# LED_sign_board_3.net
KiCad netlist of a schematic drawn in EAGLE
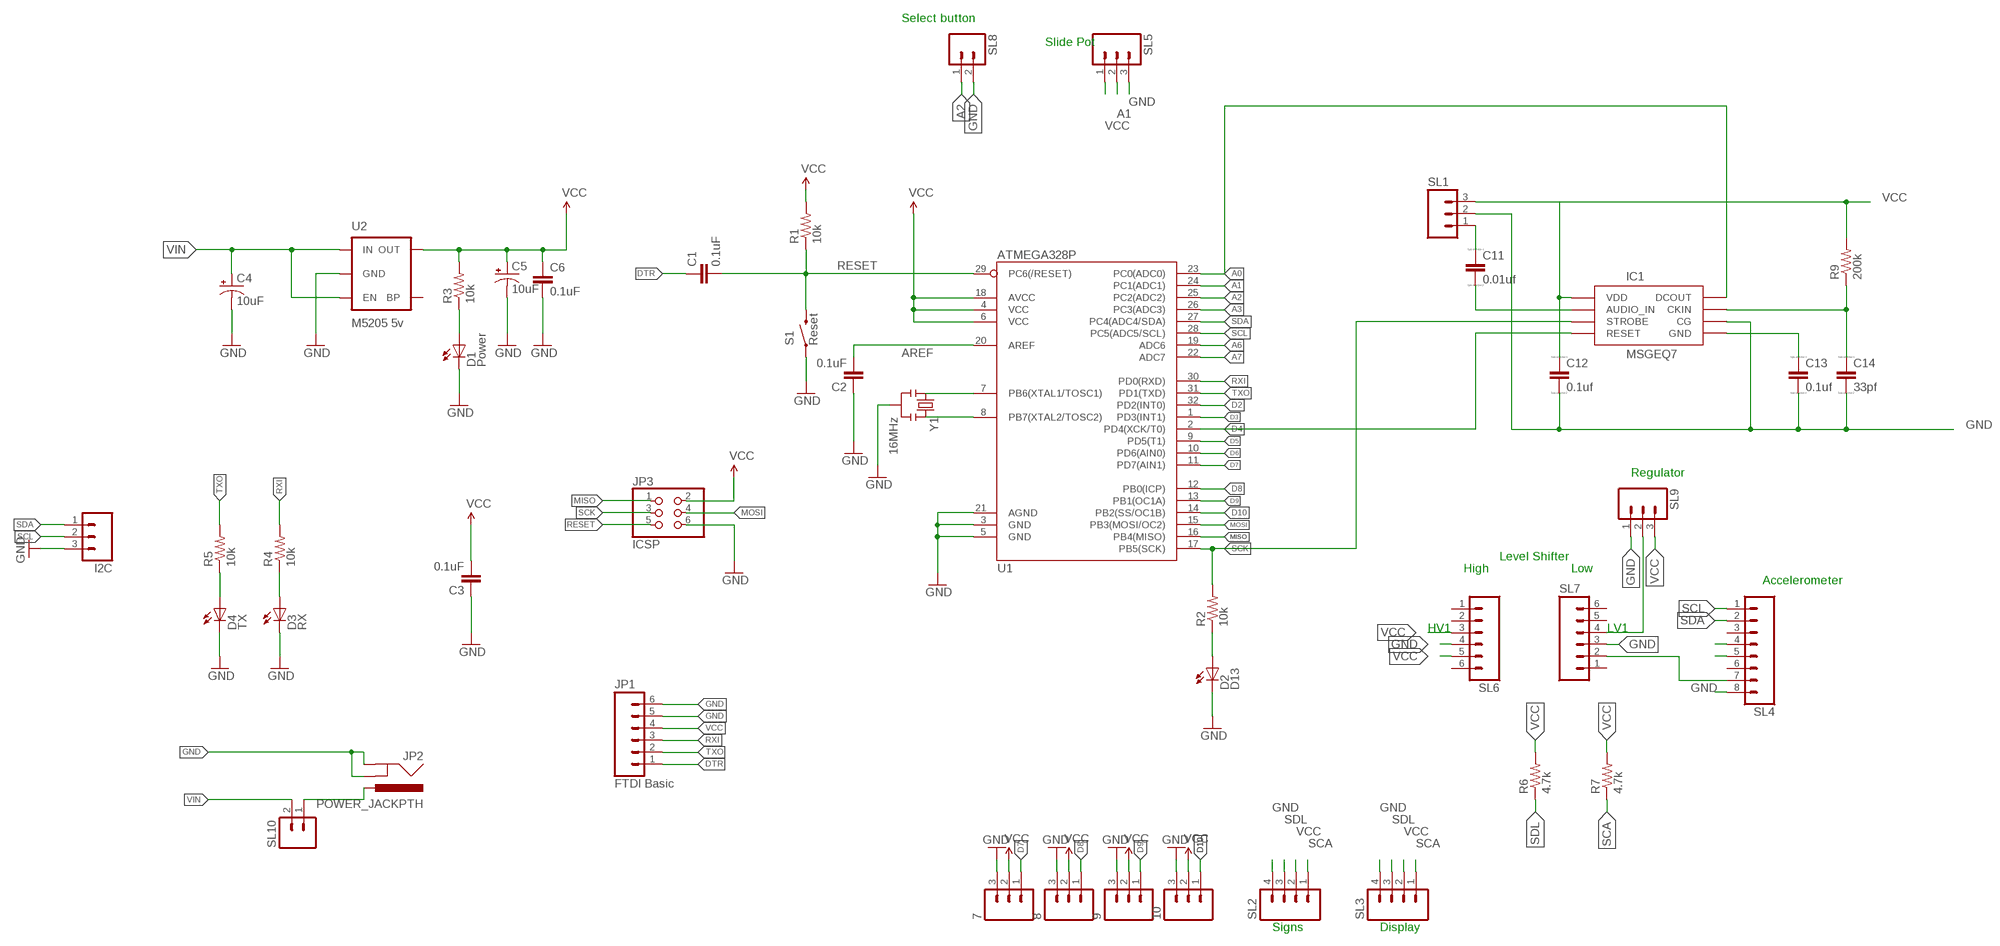
[diagram p0: schematic, sheet 1]

(export (version "E")
  (design (tool "Eeschema 10.0.6"))
  (components
    (comp (ref "7")
      (value "M03PTH")
      (footprint "eagle-import:1X03")
      (libsource (lib "eagle-import") (part "M03PTH"))
    )
    (comp (ref "8")
      (value "M03PTH")
      (footprint "eagle-import:1X03")
      (libsource (lib "eagle-import") (part "M03PTH"))
    )
    (comp (ref "9")
      (value "M03PTH")
      (footprint "eagle-import:1X03")
      (libsource (lib "eagle-import") (part "M03PTH"))
    )
    (comp (ref "10")
      (value "M03PTH")
      (footprint "eagle-import:1X03")
      (libsource (lib "eagle-import") (part "M03PTH"))
    )
    (comp (ref "C1")
      (value "0.1uF")
      (footprint "eagle-import:0603-CAP")
      (libsource (lib "eagle-import") (part "CAP0603-CAP"))
    )
    (comp (ref "C2")
      (value "0.1uF")
      (footprint "eagle-import:0603-CAP")
      (libsource (lib "eagle-import") (part "CAP0603-CAP"))
    )
    (comp (ref "C3")
      (value "0.1uF")
      (footprint "eagle-import:0603-CAP")
      (libsource (lib "eagle-import") (part "CAP0603-CAP"))
    )
    (comp (ref "C4")
      (value "10uF")
      (footprint "eagle-import:EIA3216")
      (libsource (lib "eagle-import") (part "CAP_POL1206"))
    )
    (comp (ref "C5")
      (value "10uF")
      (footprint "eagle-import:EIA3216")
      (libsource (lib "eagle-import") (part "CAP_POL1206"))
    )
    (comp (ref "C6")
      (value "0.1uF")
      (footprint "eagle-import:0603-CAP")
      (libsource (lib "eagle-import") (part "CAP0603-CAP"))
    )
    (comp (ref "C11")
      (value "0.01uf")
      (footprint "eagle-import:C0201")
      (libsource (lib "eagle-import") (part "CC0201"))
    )
    (comp (ref "C12")
      (value "0.1uf")
      (footprint "eagle-import:C0201")
      (libsource (lib "eagle-import") (part "CC0201"))
    )
    (comp (ref "C13")
      (value "0.1uf")
      (footprint "eagle-import:C0201")
      (libsource (lib "eagle-import") (part "CC0201"))
    )
    (comp (ref "C14")
      (value "33pf")
      (footprint "eagle-import:C0201")
      (libsource (lib "eagle-import") (part "CC0201"))
    )
    (comp (ref "D1")
      (value "Power")
      (footprint "eagle-import:LED-0603")
      (libsource (lib "eagle-import") (part "LED-RED0603"))
    )
    (comp (ref "D2")
      (value "D13")
      (footprint "eagle-import:LED-0603")
      (libsource (lib "eagle-import") (part "LED-RED0603"))
    )
    (comp (ref "D3")
      (value "RX")
      (footprint "eagle-import:LED-0603")
      (libsource (lib "eagle-import") (part "LED-GREEN0603"))
    )
    (comp (ref "D4")
      (value "TX")
      (footprint "eagle-import:LED-0603")
      (libsource (lib "eagle-import") (part "LED-RED0603"))
    )
    (comp (ref "I2C")
      (value "M03PTH")
      (footprint "eagle-import:1X03")
      (libsource (lib "eagle-import") (part "M03PTH"))
    )
    (comp (ref "IC1")
      (value "MSGEQ7DIL")
      (footprint "eagle-import:DIL-08")
      (libsource (lib "eagle-import") (part "MSGEQ7DIL"))
    )
    (comp (ref "JP1")
      (value "FTDI Basic")
      (footprint "eagle-import:1X06")
      (libsource (lib "eagle-import") (part "M06SIP"))
    )
    (comp (ref "JP2")
      (value "POWER_JACKPTH")
      (footprint "eagle-import:POWER_JACK_PTH")
      (libsource (lib "eagle-import") (part "POWER_JACKPTH"))
    )
    (comp (ref "JP3")
      (value "ICSP")
      (footprint "eagle-import:2X03")
      (libsource (lib "eagle-import") (part "PINHD-2X3"))
    )
    (comp (ref "R1")
      (value "10k")
      (footprint "eagle-import:0603-RES")
      (libsource (lib "eagle-import") (part "RESISTOR0603-RES"))
    )
    (comp (ref "R2")
      (value "10k")
      (footprint "eagle-import:0603-RES")
      (libsource (lib "eagle-import") (part "RESISTOR0603-RES"))
    )
    (comp (ref "R3")
      (value "10k")
      (footprint "eagle-import:0603-RES")
      (libsource (lib "eagle-import") (part "RESISTOR0603-RES"))
    )
    (comp (ref "R4")
      (value "10k")
      (footprint "eagle-import:0603-RES")
      (libsource (lib "eagle-import") (part "RESISTOR0603-RES"))
    )
    (comp (ref "R5")
      (value "10k")
      (footprint "eagle-import:0603-RES")
      (libsource (lib "eagle-import") (part "RESISTOR0603-RES"))
    )
    (comp (ref "R6")
      (value "4.7k")
      (footprint "eagle-import:1206")
      (libsource (lib "eagle-import") (part "SparkFun-Resistors_RESISTOR1206"))
    )
    (comp (ref "R7")
      (value "4.7k")
      (footprint "eagle-import:1206")
      (libsource (lib "eagle-import") (part "SparkFun-Resistors_RESISTOR1206"))
    )
    (comp (ref "R9")
      (value "200k")
      (footprint "eagle-import:1206")
      (libsource (lib "eagle-import") (part "SparkFun-Resistors_RESISTOR1206"))
    )
    (comp (ref "S1")
      (value "Reset")
      (footprint "eagle-import:TACTILE_SWITCH_SMD")
      (libsource (lib "eagle-import") (part "SWITCH-MOMENTARY-2SMD"))
    )
    (comp (ref "SL1")
      (value "M03")
      (footprint "eagle-import:03P")
      (libsource (lib "eagle-import") (part "M03"))
    )
    (comp (ref "SL2")
      (value "M04")
      (footprint "eagle-import:04P")
      (libsource (lib "eagle-import") (part "M04"))
    )
    (comp (ref "SL3")
      (value "M04")
      (footprint "eagle-import:04P")
      (libsource (lib "eagle-import") (part "M04"))
    )
    (comp (ref "SL4")
      (value "M08")
      (footprint "eagle-import:08P")
      (libsource (lib "eagle-import") (part "M08"))
    )
    (comp (ref "SL5")
      (value "M03")
      (footprint "eagle-import:03P")
      (libsource (lib "eagle-import") (part "M03"))
    )
    (comp (ref "SL6")
      (value "M06")
      (footprint "eagle-import:06P")
      (libsource (lib "eagle-import") (part "M06"))
    )
    (comp (ref "SL7")
      (value "M06")
      (footprint "eagle-import:06P")
      (libsource (lib "eagle-import") (part "M06"))
    )
    (comp (ref "SL8")
      (value "M02")
      (footprint "eagle-import:02P")
      (libsource (lib "eagle-import") (part "M02"))
    )
    (comp (ref "SL9")
      (value "M03")
      (footprint "eagle-import:03P")
      (libsource (lib "eagle-import") (part "M03"))
    )
    (comp (ref "SL10")
      (value "M02")
      (footprint "eagle-import:02P")
      (libsource (lib "eagle-import") (part "M02"))
    )
    (comp (ref "U1")
      (value "ATMEGA328P")
      (footprint "eagle-import:TQFP32-08")
      (libsource (lib "eagle-import") (part "ATMEGA328_SMT"))
    )
    (comp (ref "U2")
      (value "M5205 5v")
      (footprint "eagle-import:SOT23-5")
      (libsource (lib "eagle-import") (part "MIC52055V"))
    )
    (comp (ref "Y1")
      (value "16MHz")
      (footprint "eagle-import:RESONATOR-SMD")
      (libsource (lib "eagle-import") (part "RESONATOR16MHZ"))
    )
  )
  (nets
    (net (code "1") (name "/AREF") (class "Default")
      (node (ref "C2") (pin "2") (pinfunction "2_2") (pintype "passive"))
      (node (ref "U1") (pin "20") (pinfunction "AREF_20") (pintype "bidirectional"))
    )
    (net (code "2") (name "A0") (class "Default")
      (node (ref "IC1") (pin "3") (pinfunction "DCOUT_3") (pintype "bidirectional"))
      (node (ref "U1") (pin "23") (pinfunction "PC0(ADC0)_23") (pintype "bidirectional"))
    )
    (net (code "3") (name "A1") (class "Default")
      (node (ref "SL5") (pin "2") (pinfunction "2_2") (pintype "passive"))
      (node (ref "U1") (pin "24") (pinfunction "PC1(ADC1)_24") (pintype "bidirectional"))
    )
    (net (code "4") (name "A2") (class "Default")
      (node (ref "SL8") (pin "1") (pinfunction "1_1") (pintype "passive"))
      (node (ref "U1") (pin "25") (pinfunction "PC2(ADC2)_25") (pintype "bidirectional"))
    )
    (net (code "5") (name "A3") (class "Default")
      (node (ref "U1") (pin "26") (pinfunction "PC3(ADC3)_26") (pintype "bidirectional"))
    )
    (net (code "6") (name "A6") (class "Default")
      (node (ref "U1") (pin "19") (pinfunction "ADC6_19") (pintype "bidirectional"))
    )
    (net (code "7") (name "A7") (class "Default")
      (node (ref "U1") (pin "22") (pinfunction "ADC7_22") (pintype "bidirectional"))
    )
    (net (code "8") (name "D2") (class "Default")
      (node (ref "U1") (pin "32") (pinfunction "PD2(INT0)_32") (pintype "bidirectional"))
    )
    (net (code "9") (name "D3") (class "Default")
      (node (ref "U1") (pin "1") (pinfunction "PD3(INT1)_1") (pintype "bidirectional"))
    )
    (net (code "10") (name "D4") (class "Default")
      (node (ref "IC1") (pin "7") (pinfunction "RESET_7") (pintype "input"))
      (node (ref "U1") (pin "2") (pinfunction "PD4(XCK/T0)_2") (pintype "bidirectional"))
    )
    (net (code "11") (name "D5") (class "Default")
      (node (ref "U1") (pin "9") (pinfunction "PD5(T1)_9") (pintype "bidirectional"))
    )
    (net (code "12") (name "D6") (class "Default")
      (node (ref "U1") (pin "10") (pinfunction "PD6(AIN0)_10") (pintype "bidirectional"))
    )
    (net (code "13") (name "D7") (class "Default")
      (node (ref "7") (pin "1") (pinfunction "1_1") (pintype "passive"))
      (node (ref "U1") (pin "11") (pinfunction "PD7(AIN1)_11") (pintype "bidirectional"))
    )
    (net (code "14") (name "D8") (class "Default")
      (node (ref "8") (pin "1") (pinfunction "1_1") (pintype "passive"))
      (node (ref "U1") (pin "12") (pinfunction "PB0(ICP)_12") (pintype "bidirectional"))
    )
    (net (code "15") (name "D9") (class "Default")
      (node (ref "9") (pin "1") (pinfunction "1_1") (pintype "passive"))
      (node (ref "U1") (pin "13") (pinfunction "PB1(OC1A)_13") (pintype "bidirectional"))
    )
    (net (code "16") (name "D10") (class "Default")
      (node (ref "10") (pin "1") (pinfunction "1_1") (pintype "passive"))
      (node (ref "U1") (pin "14") (pinfunction "PB2(SS/OC1B)_14") (pintype "bidirectional"))
    )
    (net (code "17") (name "DTR") (class "Default")
      (node (ref "C1") (pin "1") (pinfunction "1_1") (pintype "passive"))
      (node (ref "JP1") (pin "1") (pinfunction "1_1") (pintype "passive"))
    )
    (net (code "18") (name "GND") (class "Default")
      (node (ref "10") (pin "3") (pinfunction "3_3") (pintype "passive"))
      (node (ref "7") (pin "3") (pinfunction "3_3") (pintype "passive"))
      (node (ref "8") (pin "3") (pinfunction "3_3") (pintype "passive"))
      (node (ref "9") (pin "3") (pinfunction "3_3") (pintype "passive"))
      (node (ref "C12") (pin "2") (pinfunction "2_2") (pintype "passive"))
      (node (ref "C13") (pin "2") (pinfunction "2_2") (pintype "passive"))
      (node (ref "C14") (pin "2") (pinfunction "2_2") (pintype "passive"))
      (node (ref "C2") (pin "1") (pinfunction "1_1") (pintype "passive"))
      (node (ref "C3") (pin "1") (pinfunction "1_1") (pintype "passive"))
      (node (ref "C4") (pin "C") (pinfunction "-_C") (pintype "passive"))
      (node (ref "C5") (pin "C") (pinfunction "-_C") (pintype "passive"))
      (node (ref "C6") (pin "2") (pinfunction "2_2") (pintype "passive"))
      (node (ref "D1") (pin "C") (pinfunction "C_C") (pintype "passive"))
      (node (ref "D2") (pin "C") (pinfunction "C_C") (pintype "passive"))
      (node (ref "D3") (pin "C") (pinfunction "C_C") (pintype "passive"))
      (node (ref "D4") (pin "C") (pinfunction "C_C") (pintype "passive"))
      (node (ref "I2C") (pin "3") (pinfunction "3_3") (pintype "passive"))
      (node (ref "IC1") (pin "6") (pinfunction "CG_6") (pintype "bidirectional"))
      (node (ref "JP1") (pin "5") (pinfunction "5_5") (pintype "passive"))
      (node (ref "JP1") (pin "6") (pinfunction "6_6") (pintype "passive"))
      (node (ref "JP2") (pin "GND") (pinfunction "GND_GND") (pintype "bidirectional"))
      (node (ref "JP2") (pin "GNDBREAK") (pinfunction "GNDBREAK_GNDBREAK") (pintype "bidirectional"))
      (node (ref "JP3") (pin "6") (pinfunction "6_6") (pintype "passive"))
      (node (ref "S1") (pin "1") (pinfunction "1_1") (pintype "passive"))
      (node (ref "SL1") (pin "2") (pinfunction "2_2") (pintype "passive"))
      (node (ref "SL2") (pin "4") (pinfunction "4_4") (pintype "passive"))
      (node (ref "SL3") (pin "4") (pinfunction "4_4") (pintype "passive"))
      (node (ref "SL4") (pin "8") (pinfunction "8_8") (pintype "passive"))
      (node (ref "SL5") (pin "3") (pinfunction "3_3") (pintype "passive"))
      (node (ref "SL6") (pin "4") (pinfunction "4_4") (pintype "passive"))
      (node (ref "SL7") (pin "3") (pinfunction "3_3") (pintype "passive"))
      (node (ref "SL7") (pin "4") (pinfunction "4_4") (pintype "passive"))
      (node (ref "SL8") (pin "2") (pinfunction "2_2") (pintype "passive"))
      (node (ref "SL9") (pin "1") (pinfunction "1_1") (pintype "passive"))
      (node (ref "SL9") (pin "2") (pinfunction "2_2") (pintype "passive"))
      (node (ref "U1") (pin "21") (pinfunction "AGND_21") (pintype "bidirectional"))
      (node (ref "U1") (pin "3") (pinfunction "GND_3") (pintype "bidirectional"))
      (node (ref "U1") (pin "5") (pinfunction "GND_5") (pintype "bidirectional"))
      (node (ref "U2") (pin "2") (pinfunction "GND_2") (pintype "input"))
      (node (ref "Y1") (pin "2") (pinfunction "2_2") (pintype "passive"))
    )
    (net (code "19") (name "MISO") (class "Default")
      (node (ref "JP3") (pin "1") (pinfunction "1_1") (pintype "passive"))
      (node (ref "U1") (pin "16") (pinfunction "PB4(MISO)_16") (pintype "bidirectional"))
    )
    (net (code "20") (name "MOSI") (class "Default")
      (node (ref "JP3") (pin "4") (pinfunction "4_4") (pintype "passive"))
      (node (ref "U1") (pin "15") (pinfunction "PB3(MOSI/OC2)_15") (pintype "bidirectional"))
    )
    (net (code "21") (name "Net-(C11-Pad1)") (class "Default")
      (node (ref "C11") (pin "1") (pinfunction "1_1") (pintype "passive"))
      (node (ref "SL1") (pin "1") (pinfunction "1_1") (pintype "passive"))
    )
    (net (code "22") (name "Net-(D1-PadA)") (class "Default")
      (node (ref "D1") (pin "A") (pinfunction "A_A") (pintype "passive"))
      (node (ref "R3") (pin "1") (pinfunction "1_1") (pintype "passive"))
    )
    (net (code "23") (name "Net-(D2-PadA)") (class "Default")
      (node (ref "D2") (pin "A") (pinfunction "A_A") (pintype "passive"))
      (node (ref "R2") (pin "1") (pinfunction "1_1") (pintype "passive"))
    )
    (net (code "24") (name "Net-(D3-PadA)") (class "Default")
      (node (ref "D3") (pin "A") (pinfunction "A_A") (pintype "passive"))
      (node (ref "R4") (pin "1") (pinfunction "1_1") (pintype "passive"))
    )
    (net (code "25") (name "Net-(D4-PadA)") (class "Default")
      (node (ref "D4") (pin "A") (pinfunction "A_A") (pintype "passive"))
      (node (ref "R5") (pin "1") (pinfunction "1_1") (pintype "passive"))
    )
    (net (code "26") (name "Net-(IC1-AUDIO_IN)") (class "Default")
      (node (ref "C11") (pin "2") (pinfunction "2_2") (pintype "passive"))
      (node (ref "IC1") (pin "5") (pinfunction "AUDIO_IN_5") (pintype "input"))
    )
    (net (code "27") (name "Net-(IC1-CKIN)") (class "Default")
      (node (ref "C14") (pin "1") (pinfunction "1_1") (pintype "passive"))
      (node (ref "IC1") (pin "8") (pinfunction "CKIN_8") (pintype "bidirectional"))
      (node (ref "R9") (pin "1") (pinfunction "1_1") (pintype "passive"))
    )
    (net (code "28") (name "Net-(IC1-GND)") (class "Default")
      (node (ref "C13") (pin "1") (pinfunction "1_1") (pintype "passive"))
      (node (ref "IC1") (pin "2") (pinfunction "GND_2") (pintype "bidirectional"))
    )
    (net (code "29") (name "Net-(JP2-PadPWR)") (class "Default")
      (node (ref "JP2") (pin "PWR") (pinfunction "PWR_PWR") (pintype "bidirectional"))
      (node (ref "SL10") (pin "1") (pinfunction "1_1") (pintype "passive"))
    )
    (net (code "30") (name "Net-(SL4-Pad7)") (class "Default")
      (node (ref "SL4") (pin "7") (pinfunction "7_7") (pintype "passive"))
      (node (ref "SL7") (pin "2") (pinfunction "2_2") (pintype "passive"))
    )
    (net (code "31") (name "Net-(U1-PB6(XTAL1{slash}TOSC1))") (class "Default")
      (node (ref "U1") (pin "7") (pinfunction "PB6(XTAL1/TOSC1)_7") (pintype "bidirectional"))
      (node (ref "Y1") (pin "1") (pinfunction "1_1") (pintype "passive"))
    )
    (net (code "32") (name "Net-(U1-PB7(XTAL2{slash}TOSC2))") (class "Default")
      (node (ref "U1") (pin "8") (pinfunction "PB7(XTAL2/TOSC2)_8") (pintype "bidirectional"))
      (node (ref "Y1") (pin "3") (pinfunction "3_3") (pintype "passive"))
    )
    (net (code "33") (name "RESET") (class "Default")
      (node (ref "C1") (pin "2") (pinfunction "2_2") (pintype "passive"))
      (node (ref "JP3") (pin "5") (pinfunction "5_5") (pintype "passive"))
      (node (ref "R1") (pin "1") (pinfunction "1_1") (pintype "passive"))
      (node (ref "S1") (pin "3") (pinfunction "2_3") (pintype "passive"))
      (node (ref "U1") (pin "29") (pinfunction "PC6(/RESET)_29") (pintype "bidirectional"))
    )
    (net (code "34") (name "RXI") (class "Default")
      (node (ref "JP1") (pin "3") (pinfunction "3_3") (pintype "passive"))
      (node (ref "R4") (pin "2") (pinfunction "2_2") (pintype "passive"))
      (node (ref "U1") (pin "30") (pinfunction "PD0(RXD)_30") (pintype "bidirectional"))
    )
    (net (code "35") (name "SCA") (class "Default")
      (node (ref "R7") (pin "1") (pinfunction "1_1") (pintype "passive"))
      (node (ref "SL2") (pin "1") (pinfunction "1_1") (pintype "passive"))
      (node (ref "SL3") (pin "1") (pinfunction "1_1") (pintype "passive"))
    )
    (net (code "36") (name "SCK") (class "Default")
      (node (ref "IC1") (pin "4") (pinfunction "STROBE_4") (pintype "input"))
      (node (ref "JP3") (pin "3") (pinfunction "3_3") (pintype "passive"))
      (node (ref "R2") (pin "2") (pinfunction "2_2") (pintype "passive"))
      (node (ref "U1") (pin "17") (pinfunction "PB5(SCK)_17") (pintype "bidirectional"))
    )
    (net (code "37") (name "SCL") (class "Default")
      (node (ref "I2C") (pin "2") (pinfunction "2_2") (pintype "passive"))
      (node (ref "SL4") (pin "1") (pinfunction "1_1") (pintype "passive"))
      (node (ref "U1") (pin "28") (pinfunction "PC5(ADC5/SCL)_28") (pintype "bidirectional"))
    )
    (net (code "38") (name "SDA") (class "Default")
      (node (ref "I2C") (pin "1") (pinfunction "1_1") (pintype "passive"))
      (node (ref "SL4") (pin "2") (pinfunction "2_2") (pintype "passive"))
      (node (ref "U1") (pin "27") (pinfunction "PC4(ADC4/SDA)_27") (pintype "bidirectional"))
    )
    (net (code "39") (name "SDL") (class "Default")
      (node (ref "R6") (pin "1") (pinfunction "1_1") (pintype "passive"))
      (node (ref "SL2") (pin "3") (pinfunction "3_3") (pintype "passive"))
      (node (ref "SL3") (pin "3") (pinfunction "3_3") (pintype "passive"))
    )
    (net (code "40") (name "TXO") (class "Default")
      (node (ref "JP1") (pin "2") (pinfunction "2_2") (pintype "passive"))
      (node (ref "R5") (pin "2") (pinfunction "2_2") (pintype "passive"))
      (node (ref "U1") (pin "31") (pinfunction "PD1(TXD)_31") (pintype "bidirectional"))
    )
    (net (code "41") (name "VCC") (class "Default")
      (node (ref "10") (pin "2") (pinfunction "2_2") (pintype "passive"))
      (node (ref "7") (pin "2") (pinfunction "2_2") (pintype "passive"))
      (node (ref "8") (pin "2") (pinfunction "2_2") (pintype "passive"))
      (node (ref "9") (pin "2") (pinfunction "2_2") (pintype "passive"))
      (node (ref "C12") (pin "1") (pinfunction "1_1") (pintype "passive"))
      (node (ref "C3") (pin "2") (pinfunction "2_2") (pintype "passive"))
      (node (ref "C5") (pin "A") (pinfunction "+_A") (pintype "passive"))
      (node (ref "C6") (pin "1") (pinfunction "1_1") (pintype "passive"))
      (node (ref "IC1") (pin "1") (pinfunction "VDD_1") (pintype "input"))
      (node (ref "JP1") (pin "4") (pinfunction "4_4") (pintype "passive"))
      (node (ref "JP3") (pin "2") (pinfunction "2_2") (pintype "passive"))
      (node (ref "R1") (pin "2") (pinfunction "2_2") (pintype "passive"))
      (node (ref "R3") (pin "2") (pinfunction "2_2") (pintype "passive"))
      (node (ref "R6") (pin "2") (pinfunction "2_2") (pintype "passive"))
      (node (ref "R7") (pin "2") (pinfunction "2_2") (pintype "passive"))
      (node (ref "R9") (pin "2") (pinfunction "2_2") (pintype "passive"))
      (node (ref "SL1") (pin "3") (pinfunction "3_3") (pintype "passive"))
      (node (ref "SL2") (pin "2") (pinfunction "2_2") (pintype "passive"))
      (node (ref "SL3") (pin "2") (pinfunction "2_2") (pintype "passive"))
      (node (ref "SL5") (pin "1") (pinfunction "1_1") (pintype "passive"))
      (node (ref "SL6") (pin "3") (pinfunction "3_3") (pintype "passive"))
      (node (ref "SL6") (pin "5") (pinfunction "5_5") (pintype "passive"))
      (node (ref "SL9") (pin "3") (pinfunction "3_3") (pintype "passive"))
      (node (ref "U1") (pin "18") (pinfunction "AVCC_18") (pintype "bidirectional"))
      (node (ref "U1") (pin "4") (pinfunction "VCC_4") (pintype "bidirectional"))
      (node (ref "U1") (pin "6") (pinfunction "VCC_6") (pintype "bidirectional"))
      (node (ref "U2") (pin "5") (pinfunction "OUT_5") (pintype "passive"))
    )
    (net (code "42") (name "VIN") (class "Default")
      (node (ref "C4") (pin "A") (pinfunction "+_A") (pintype "passive"))
      (node (ref "SL10") (pin "2") (pinfunction "2_2") (pintype "passive"))
      (node (ref "U2") (pin "1") (pinfunction "IN_1") (pintype "input"))
      (node (ref "U2") (pin "3") (pinfunction "EN_3") (pintype "input"))
    )
    (net (code "43") (name "unconnected-(SL4-Pad3)") (class "Default")
      (node (ref "SL4") (pin "3") (pinfunction "3_3") (pintype "passive"))
    )
    (net (code "44") (name "unconnected-(SL4-Pad4)") (class "Default")
      (node (ref "SL4") (pin "4") (pinfunction "4_4") (pintype "passive"))
    )
    (net (code "45") (name "unconnected-(SL4-Pad5)") (class "Default")
      (node (ref "SL4") (pin "5") (pinfunction "5_5") (pintype "passive"))
    )
    (net (code "46") (name "unconnected-(SL4-Pad6)") (class "Default")
      (node (ref "SL4") (pin "6") (pinfunction "6_6") (pintype "passive"))
    )
    (net (code "47") (name "unconnected-(SL6-Pad1)") (class "Default")
      (node (ref "SL6") (pin "1") (pinfunction "1_1") (pintype "passive"))
    )
    (net (code "48") (name "unconnected-(SL6-Pad2)") (class "Default")
      (node (ref "SL6") (pin "2") (pinfunction "2_2") (pintype "passive"))
    )
    (net (code "49") (name "unconnected-(SL6-Pad6)") (class "Default")
      (node (ref "SL6") (pin "6") (pinfunction "6_6") (pintype "passive"))
    )
    (net (code "50") (name "unconnected-(SL7-Pad1)") (class "Default")
      (node (ref "SL7") (pin "1") (pinfunction "1_1") (pintype "passive"))
    )
    (net (code "51") (name "unconnected-(SL7-Pad5)") (class "Default")
      (node (ref "SL7") (pin "5") (pinfunction "5_5") (pintype "passive"))
    )
    (net (code "52") (name "unconnected-(SL7-Pad6)") (class "Default")
      (node (ref "SL7") (pin "6") (pinfunction "6_6") (pintype "passive"))
    )
    (net (code "53") (name "unconnected-(U2-BP-Pad4)") (class "Default")
      (node (ref "U2") (pin "4") (pinfunction "BP_4") (pintype "input"))
    )
  )
)
